# hyone.net
KiCad netlist of a schematic drawn in EAGLE
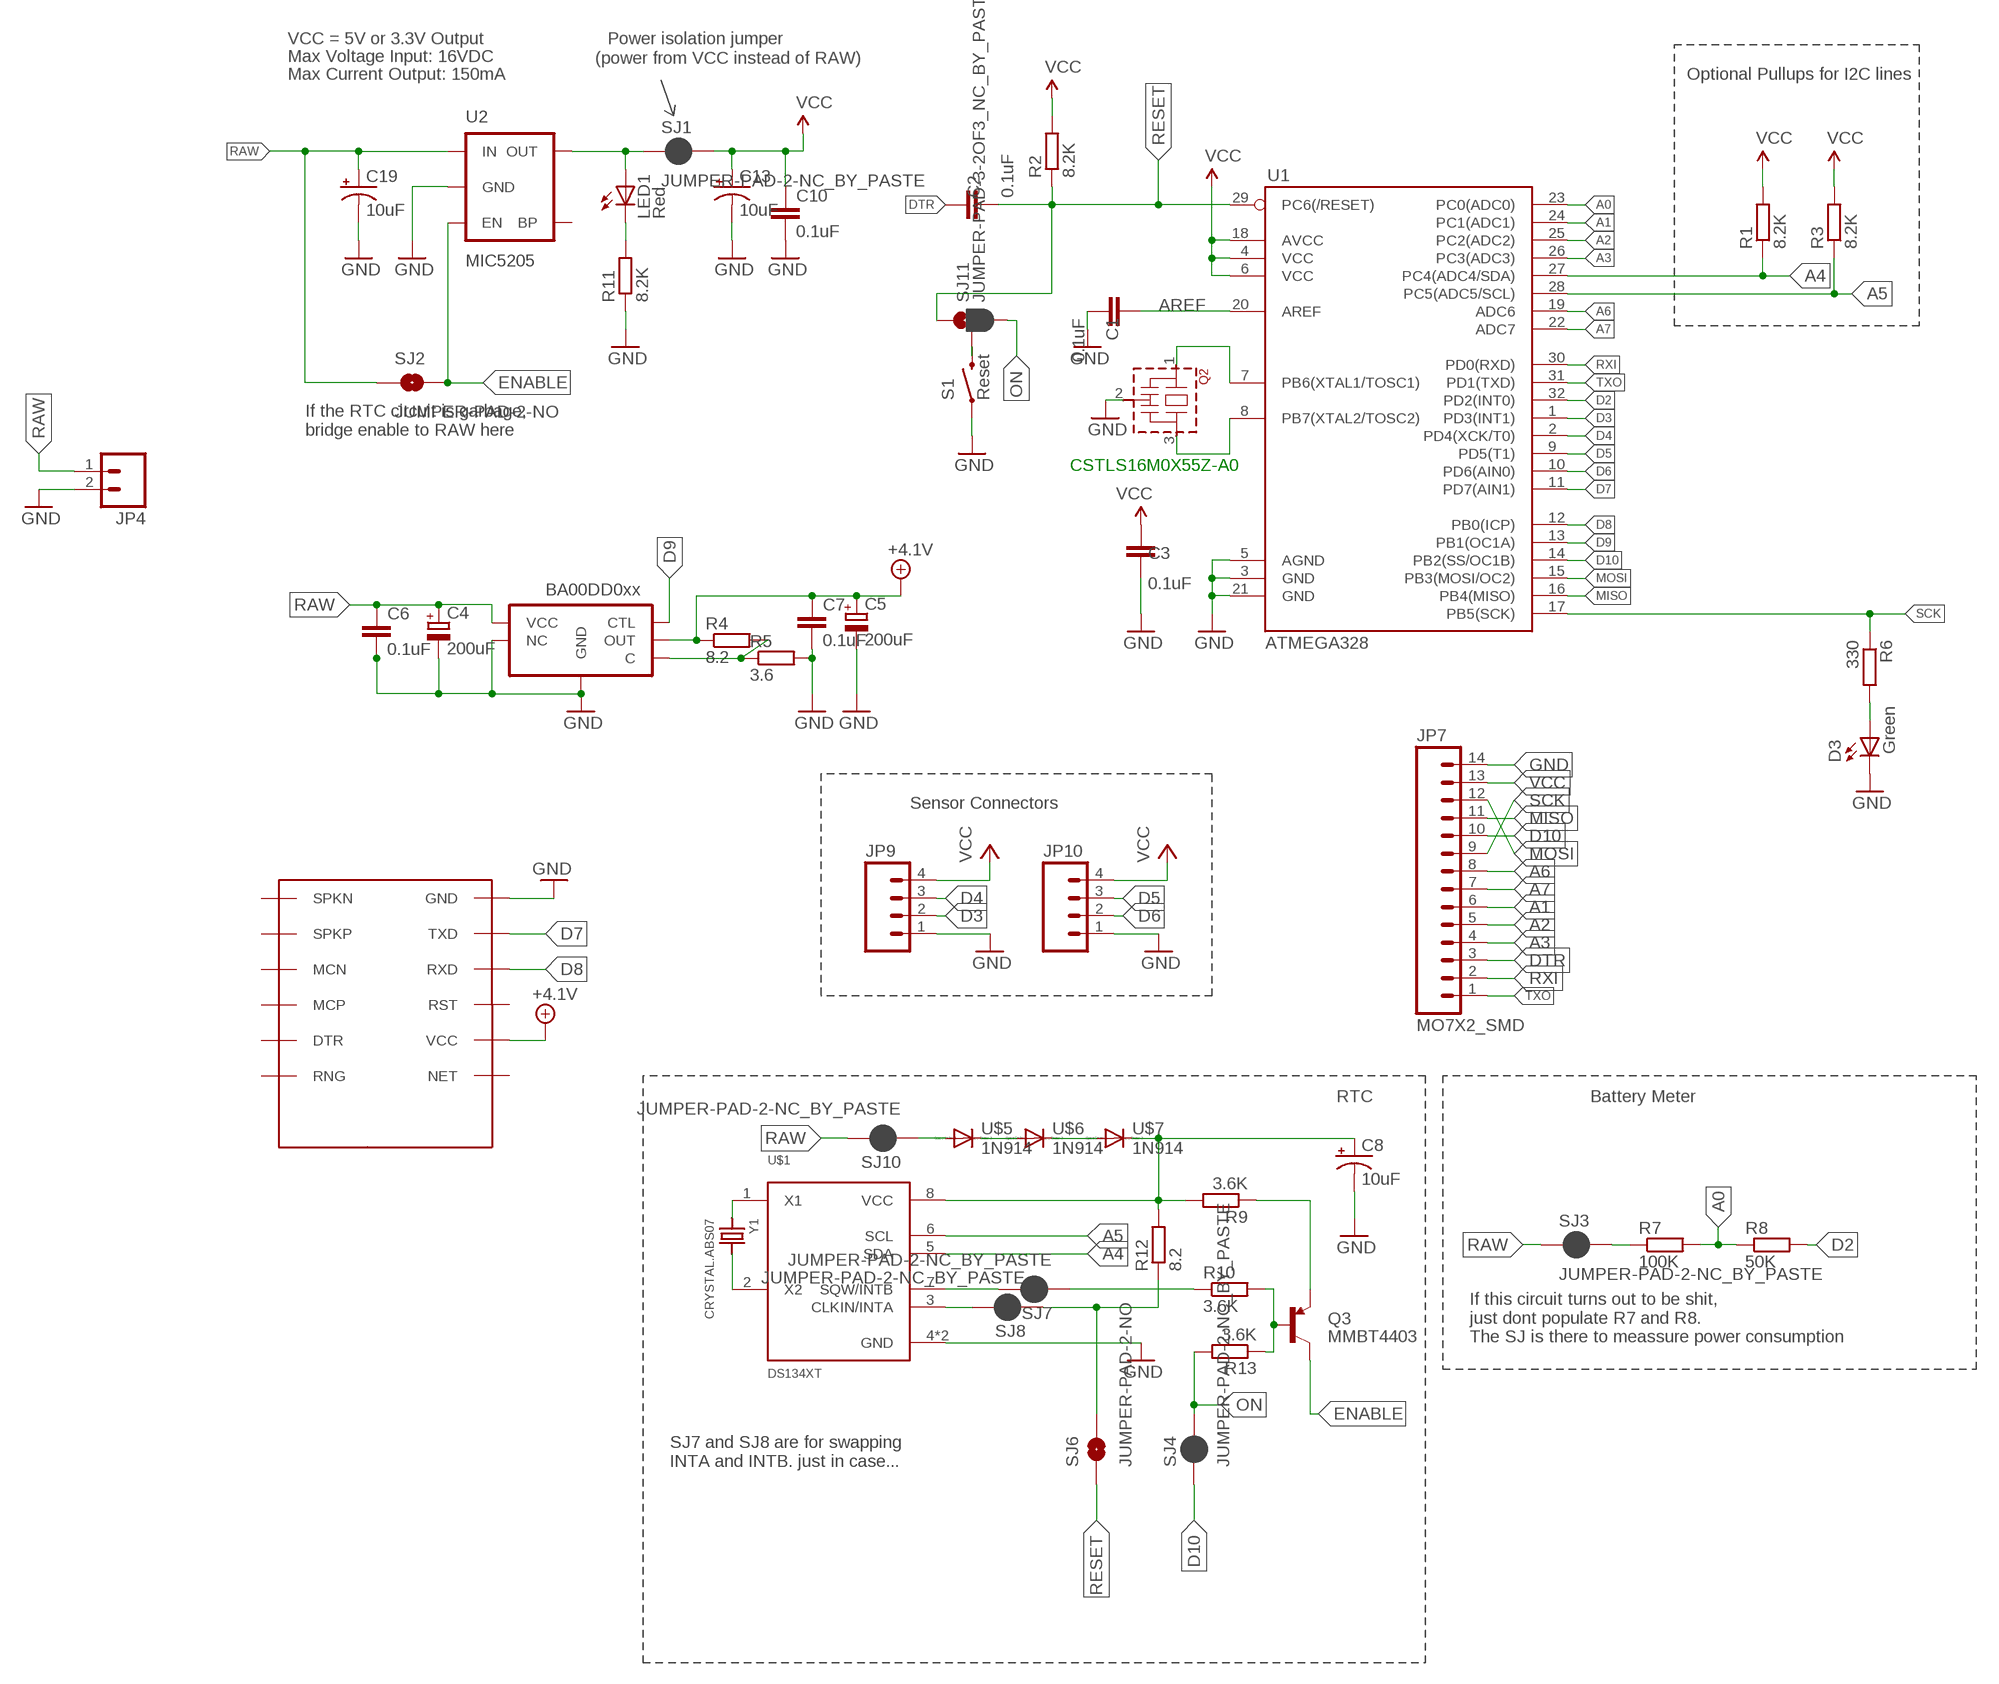
[diagram p0: schematic, sheet 1]

(export (version "E")
  (design (tool "Eeschema 10.0.6"))
  (components
    (comp (ref "C1")
      (value "0.1uF")
      (footprint "eagle-import:C0805")
      (libsource (lib "eagle-import") (part "C-EUC0805"))
    )
    (comp (ref "C2")
      (value "0.1uF")
      (footprint "eagle-import:C0805")
      (libsource (lib "eagle-import") (part "C-EUC0805"))
    )
    (comp (ref "C3")
      (value "0.1uF")
      (footprint "eagle-import:C0805")
      (libsource (lib "eagle-import") (part "C-EUC0805"))
    )
    (comp (ref "C4")
      (value "200uF")
      (footprint "eagle-import:E5-5")
      (libsource (lib "eagle-import") (part "CPOL-EUE5-5"))
    )
    (comp (ref "C5")
      (value "200uF")
      (footprint "eagle-import:E5-5")
      (libsource (lib "eagle-import") (part "CPOL-EUE5-5"))
    )
    (comp (ref "C6")
      (value "0.1uF")
      (footprint "eagle-import:C0805")
      (libsource (lib "eagle-import") (part "C-EUC0805"))
    )
    (comp (ref "C7")
      (value "0.1uF")
      (footprint "eagle-import:C0805")
      (libsource (lib "eagle-import") (part "C-EUC0805"))
    )
    (comp (ref "C8")
      (value "10uF")
      (footprint "eagle-import:EIA3216")
      (libsource (lib "eagle-import") (part "CAP_POL1206"))
    )
    (comp (ref "C10")
      (value "0.1uF")
      (footprint "eagle-import:C0805")
      (libsource (lib "eagle-import") (part "C-EUC0805"))
    )
    (comp (ref "C13")
      (value "10uF")
      (footprint "eagle-import:EIA3216")
      (libsource (lib "eagle-import") (part "CAP_POL1206"))
    )
    (comp (ref "C19")
      (value "10uF")
      (footprint "eagle-import:EIA3216")
      (libsource (lib "eagle-import") (part "CAP_POL1206"))
    )
    (comp (ref "D3")
      (value "Green")
      (footprint "eagle-import:CHIPLED_0805")
      (libsource (lib "eagle-import") (part "LEDCHIPLED_0805"))
    )
    (comp (ref "JP4")
      (value "M02POLAR")
      (footprint "eagle-import:MOLEX-1X2")
      (libsource (lib "eagle-import") (part "M02POLAR"))
    )
    (comp (ref "JP7")
      (value "MO7X2_SMD")
      (footprint "eagle-import:2X7_SMD")
      (libsource (lib "eagle-import") (part "MO7X2_SMD"))
    )
    (comp (ref "JP9")
      (value "M04POLAR")
      (footprint "eagle-import:MOLEX-1X4")
      (libsource (lib "eagle-import") (part "M04POLAR"))
    )
    (comp (ref "JP10")
      (value "M04POLAR")
      (footprint "eagle-import:MOLEX-1X4")
      (libsource (lib "eagle-import") (part "M04POLAR"))
    )
    (comp (ref "LED1")
      (value "Red")
      (footprint "eagle-import:CHIPLED_0805")
      (libsource (lib "eagle-import") (part "LEDCHIPLED_0805"))
    )
    (comp (ref "Q2")
      (value "CSTLS_X")
      (footprint "eagle-import:CSTLS_X")
      (libsource (lib "eagle-import") (part "CSTLS_X"))
    )
    (comp (ref "Q3")
      (value "MMBT4403")
      (footprint "eagle-import:SOT23-3")
      (libsource (lib "eagle-import") (part "TRANSISTOR_PNPMMBT4403"))
    )
    (comp (ref "R1")
      (value "8.2K")
      (footprint "eagle-import:R1206")
      (libsource (lib "eagle-import") (part "R-EU_R1206"))
    )
    (comp (ref "R2")
      (value "8.2K")
      (footprint "eagle-import:R1206")
      (libsource (lib "eagle-import") (part "R-EU_R1206"))
    )
    (comp (ref "R3")
      (value "8.2K")
      (footprint "eagle-import:R1206")
      (libsource (lib "eagle-import") (part "R-EU_R1206"))
    )
    (comp (ref "R4")
      (value "8.2")
      (footprint "eagle-import:R1206")
      (libsource (lib "eagle-import") (part "resistor_R-EU_R1206"))
    )
    (comp (ref "R5")
      (value "3.6")
      (footprint "eagle-import:R1206")
      (libsource (lib "eagle-import") (part "resistor_R-EU_R1206"))
    )
    (comp (ref "R6")
      (value "330")
      (footprint "eagle-import:R1206")
      (libsource (lib "eagle-import") (part "R-EU_R1206"))
    )
    (comp (ref "R7")
      (value "100K")
      (footprint "eagle-import:R1206")
      (libsource (lib "eagle-import") (part "resistor_R-EU_R1206"))
    )
    (comp (ref "R8")
      (value "50K")
      (footprint "eagle-import:R1206")
      (libsource (lib "eagle-import") (part "resistor_R-EU_R1206"))
    )
    (comp (ref "R9")
      (value "3.6K")
      (footprint "eagle-import:R1206")
      (libsource (lib "eagle-import") (part "R-EU_R1206"))
    )
    (comp (ref "R10")
      (value "3.6K")
      (footprint "eagle-import:R1206")
      (libsource (lib "eagle-import") (part "R-EU_R1206"))
    )
    (comp (ref "R11")
      (value "8.2K")
      (footprint "eagle-import:R1206")
      (libsource (lib "eagle-import") (part "R-EU_R1206"))
    )
    (comp (ref "R12")
      (value "8.2")
      (footprint "eagle-import:R1206")
      (libsource (lib "eagle-import") (part "resistor_R-EU_R1206"))
    )
    (comp (ref "R13")
      (value "3.6K")
      (footprint "eagle-import:R1206")
      (libsource (lib "eagle-import") (part "R-EU_R1206"))
    )
    (comp (ref "S1")
      (value "Reset")
      (footprint "eagle-import:TACTILE-SWITCH-SMD-ALT01")
      (libsource (lib "eagle-import") (part "SWITCH-MOMENTARY-2SMD-ALT01"))
    )
    (comp (ref "SJ1")
      (value "JUMPER-PAD-2-NC_BY_PASTE")
      (footprint "eagle-import:PAD-JUMPER-2-NC_BY_PASTE_YES_SILK")
      (libsource (lib "eagle-import") (part "JUMPER-PAD-2-NC_BY_PASTE"))
    )
    (comp (ref "SJ2")
      (value "JUMPER-PAD-2-NO")
      (footprint "eagle-import:PAD-JUMPER-2-NO_NO_SILK")
      (libsource (lib "eagle-import") (part "JUMPER-PAD-2-NO"))
    )
    (comp (ref "SJ3")
      (value "JUMPER-PAD-2-NC_BY_PASTE")
      (footprint "eagle-import:PAD-JUMPER-2-NC_BY_PASTE_YES_SILK")
      (libsource (lib "eagle-import") (part "JUMPER-PAD-2-NC_BY_PASTE"))
    )
    (comp (ref "SJ4")
      (value "JUMPER-PAD-2-NC_BY_PASTE")
      (footprint "eagle-import:PAD-JUMPER-2-NC_BY_PASTE_YES_SILK")
      (libsource (lib "eagle-import") (part "JUMPER-PAD-2-NC_BY_PASTE"))
    )
    (comp (ref "SJ6")
      (value "JUMPER-PAD-2-NO")
      (footprint "eagle-import:PAD-JUMPER-2-NO_NO_SILK")
      (libsource (lib "eagle-import") (part "JUMPER-PAD-2-NO"))
    )
    (comp (ref "SJ7")
      (value "JUMPER-PAD-2-NC_BY_PASTE")
      (footprint "eagle-import:PAD-JUMPER-2-NC_BY_PASTE_YES_SILK")
      (libsource (lib "eagle-import") (part "JUMPER-PAD-2-NC_BY_PASTE"))
    )
    (comp (ref "SJ8")
      (value "JUMPER-PAD-2-NC_BY_PASTE")
      (footprint "eagle-import:PAD-JUMPER-2-NC_BY_PASTE_YES_SILK")
      (libsource (lib "eagle-import") (part "JUMPER-PAD-2-NC_BY_PASTE"))
    )
    (comp (ref "SJ10")
      (value "JUMPER-PAD-2-NC_BY_PASTE")
      (footprint "eagle-import:PAD-JUMPER-2-NC_BY_PASTE_YES_SILK")
      (libsource (lib "eagle-import") (part "JUMPER-PAD-2-NC_BY_PASTE"))
    )
    (comp (ref "SJ11")
      (value "JUMPER-PAD-3-2OF3_NC_BY_PASTE")
      (footprint "eagle-import:PAD-JUMPER-3-2OF3_NC_BY_PASTE_YES_SILK_FULL_BOX")
      (libsource (lib "eagle-import") (part "JUMPER-PAD-3-2OF3_NC_BY_PASTE"))
    )
    (comp (ref "U$1")
      (value "DS134XT")
      (footprint "eagle-import:TDFN-8")
      (libsource (lib "eagle-import") (part "DS134XT"))
    )
    (comp (ref "U$2")
      (value "BA00DD0XX")
      (footprint "eagle-import:HRP5")
      (libsource (lib "eagle-import") (part "BA00DD0XX"))
    )
    (comp (ref "U$4")
      (value "SIM800L")
      (footprint "eagle-import:SIM-CORE")
      (libsource (lib "eagle-import") (part "SIM800L"))
    )
    (comp (ref "U$5")
      (value "1N914")
      (footprint "eagle-import:SOT23")
      (libsource (lib "eagle-import") (part "1N914"))
    )
    (comp (ref "U$6")
      (value "1N914")
      (footprint "eagle-import:SOT23")
      (libsource (lib "eagle-import") (part "1N914"))
    )
    (comp (ref "U$7")
      (value "1N914")
      (footprint "eagle-import:SOT23")
      (libsource (lib "eagle-import") (part "1N914"))
    )
    (comp (ref "U1")
      (value "ATMEGA328")
      (footprint "eagle-import:TQFP32-08")
      (libsource (lib "eagle-import") (part "ATMEGA168"))
    )
    (comp (ref "U2")
      (value "MIC5205")
      (footprint "eagle-import:SOT23-5")
      (libsource (lib "eagle-import") (part "V_REG_LDOSMD"))
    )
    (comp (ref "Y1")
      (value "CRYSTAL.ABS07")
      (footprint "eagle-import:ABS07")
      (libsource (lib "eagle-import") (part "CRYSTAL.ABS07"))
    )
  )
  (nets
    (net (code "1") (name "+4.1V") (class "Default")
      (node (ref "C5") (pin "+") (pinfunction "+_+") (pintype "passive"))
      (node (ref "C7") (pin "1") (pinfunction "1_1") (pintype "passive"))
      (node (ref "R4") (pin "1") (pinfunction "1_1") (pintype "passive"))
      (node (ref "U$2") (pin "4") (pinfunction "OUT_4") (pintype "bidirectional"))
      (node (ref "U$4") (pin "VCC") (pinfunction "VCC_VCC") (pintype "bidirectional"))
    )
    (net (code "2") (name "/AREF") (class "Default")
      (node (ref "C1") (pin "2") (pinfunction "2_2") (pintype "passive"))
      (node (ref "U1") (pin "20") (pinfunction "AREF_20") (pintype "bidirectional"))
    )
    (net (code "3") (name "A0") (class "Default")
      (node (ref "R7") (pin "2") (pinfunction "2_2") (pintype "passive"))
      (node (ref "R8") (pin "1") (pinfunction "1_1") (pintype "passive"))
      (node (ref "U1") (pin "23") (pinfunction "PC0(ADC0)_23") (pintype "bidirectional"))
    )
    (net (code "4") (name "A1") (class "Default")
      (node (ref "JP7") (pin "6") (pinfunction "6_6") (pintype "passive"))
      (node (ref "U1") (pin "24") (pinfunction "PC1(ADC1)_24") (pintype "bidirectional"))
    )
    (net (code "5") (name "A2") (class "Default")
      (node (ref "JP7") (pin "5") (pinfunction "5_5") (pintype "passive"))
      (node (ref "U1") (pin "25") (pinfunction "PC2(ADC2)_25") (pintype "bidirectional"))
    )
    (net (code "6") (name "A3") (class "Default")
      (node (ref "JP7") (pin "4") (pinfunction "4_4") (pintype "passive"))
      (node (ref "U1") (pin "26") (pinfunction "PC3(ADC3)_26") (pintype "bidirectional"))
    )
    (net (code "7") (name "A4") (class "Default")
      (node (ref "R1") (pin "1") (pinfunction "1_1") (pintype "passive"))
      (node (ref "U$1") (pin "5") (pinfunction "SDA_5") (pintype "bidirectional"))
      (node (ref "U1") (pin "27") (pinfunction "PC4(ADC4/SDA)_27") (pintype "bidirectional"))
    )
    (net (code "8") (name "A5") (class "Default")
      (node (ref "R3") (pin "1") (pinfunction "1_1") (pintype "passive"))
      (node (ref "U$1") (pin "6") (pinfunction "SCL_6") (pintype "bidirectional"))
      (node (ref "U1") (pin "28") (pinfunction "PC5(ADC5/SCL)_28") (pintype "bidirectional"))
    )
    (net (code "9") (name "A6") (class "Default")
      (node (ref "JP7") (pin "8") (pinfunction "8_8") (pintype "passive"))
      (node (ref "U1") (pin "19") (pinfunction "ADC6_19") (pintype "bidirectional"))
    )
    (net (code "10") (name "A7") (class "Default")
      (node (ref "JP7") (pin "7") (pinfunction "7_7") (pintype "passive"))
      (node (ref "U1") (pin "22") (pinfunction "ADC7_22") (pintype "bidirectional"))
    )
    (net (code "11") (name "D2") (class "Default")
      (node (ref "R8") (pin "2") (pinfunction "2_2") (pintype "passive"))
      (node (ref "U1") (pin "32") (pinfunction "PD2(INT0)_32") (pintype "bidirectional"))
    )
    (net (code "12") (name "D3") (class "Default")
      (node (ref "JP9") (pin "2") (pinfunction "2_2") (pintype "passive"))
      (node (ref "U1") (pin "1") (pinfunction "PD3(INT1)_1") (pintype "bidirectional"))
    )
    (net (code "13") (name "D4") (class "Default")
      (node (ref "JP9") (pin "3") (pinfunction "3_3") (pintype "passive"))
      (node (ref "U1") (pin "2") (pinfunction "PD4(XCK/T0)_2") (pintype "bidirectional"))
    )
    (net (code "14") (name "D5") (class "Default")
      (node (ref "JP10") (pin "3") (pinfunction "3_3") (pintype "passive"))
      (node (ref "U1") (pin "9") (pinfunction "PD5(T1)_9") (pintype "bidirectional"))
    )
    (net (code "15") (name "D6") (class "Default")
      (node (ref "JP10") (pin "2") (pinfunction "2_2") (pintype "passive"))
      (node (ref "U1") (pin "10") (pinfunction "PD6(AIN0)_10") (pintype "bidirectional"))
    )
    (net (code "16") (name "D7") (class "Default")
      (node (ref "U$4") (pin "TXD") (pinfunction "TXD_TXD") (pintype "bidirectional"))
      (node (ref "U1") (pin "11") (pinfunction "PD7(AIN1)_11") (pintype "bidirectional"))
    )
    (net (code "17") (name "D8") (class "Default")
      (node (ref "U$4") (pin "RXD") (pinfunction "RXD_RXD") (pintype "bidirectional"))
      (node (ref "U1") (pin "12") (pinfunction "PB0(ICP)_12") (pintype "bidirectional"))
    )
    (net (code "18") (name "D9") (class "Default")
      (node (ref "U$2") (pin "1") (pinfunction "CTL_1") (pintype "bidirectional"))
      (node (ref "U1") (pin "13") (pinfunction "PB1(OC1A)_13") (pintype "bidirectional"))
    )
    (net (code "19") (name "D10") (class "Default")
      (node (ref "JP7") (pin "10") (pinfunction "10_10") (pintype "passive"))
      (node (ref "SJ4") (pin "1") (pinfunction "1_1") (pintype "passive"))
      (node (ref "U1") (pin "14") (pinfunction "PB2(SS/OC1B)_14") (pintype "bidirectional"))
    )
    (net (code "20") (name "DTR") (class "Default")
      (node (ref "C2") (pin "2") (pinfunction "2_2") (pintype "passive"))
      (node (ref "JP7") (pin "3") (pinfunction "3_3") (pintype "passive"))
    )
    (net (code "21") (name "ENABLE") (class "Default")
      (node (ref "Q3") (pin "3") (pinfunction "C_3") (pintype "passive"))
      (node (ref "SJ2") (pin "2") (pinfunction "2_2") (pintype "passive"))
      (node (ref "U2") (pin "3") (pinfunction "EN_3") (pintype "input"))
    )
    (net (code "22") (name "GND") (class "Default")
      (node (ref "C1") (pin "1") (pinfunction "1_1") (pintype "passive"))
      (node (ref "C10") (pin "2") (pinfunction "2_2") (pintype "passive"))
      (node (ref "C13") (pin "C") (pinfunction "-_C") (pintype "passive"))
      (node (ref "C19") (pin "C") (pinfunction "-_C") (pintype "passive"))
      (node (ref "C3") (pin "1") (pinfunction "1_1") (pintype "passive"))
      (node (ref "C4") (pin "-") (pinfunction "-_-") (pintype "passive"))
      (node (ref "C5") (pin "-") (pinfunction "-_-") (pintype "passive"))
      (node (ref "C6") (pin "2") (pinfunction "2_2") (pintype "passive"))
      (node (ref "C7") (pin "2") (pinfunction "2_2") (pintype "passive"))
      (node (ref "C8") (pin "C") (pinfunction "-_C") (pintype "passive"))
      (node (ref "D3") (pin "C") (pinfunction "C_C") (pintype "passive"))
      (node (ref "JP10") (pin "1") (pinfunction "1_1") (pintype "passive"))
      (node (ref "JP4") (pin "2") (pinfunction "2_2") (pintype "passive"))
      (node (ref "JP7") (pin "14") (pinfunction "14_14") (pintype "passive"))
      (node (ref "JP9") (pin "1") (pinfunction "1_1") (pintype "passive"))
      (node (ref "Q2") (pin "2") (pinfunction "VSS_2") (pintype "power_in"))
      (node (ref "R11") (pin "1") (pinfunction "1_1") (pintype "passive"))
      (node (ref "R5") (pin "2") (pinfunction "2_2") (pintype "passive"))
      (node (ref "S1") (pin "1") (pinfunction "1_1") (pintype "passive"))
      (node (ref "S1") (pin "2") (pinfunction "1_2") (pintype "passive"))
      (node (ref "U$1") (pin "4") (pinfunction "GND_4") (pintype "bidirectional"))
      (node (ref "U$1") (pin "EP") (pinfunction "GND_EP") (pintype "bidirectional"))
      (node (ref "U$2") (pin "3") (pinfunction "NC_3") (pintype "bidirectional"))
      (node (ref "U$2") (pin "6") (pinfunction "GND_6") (pintype "bidirectional"))
      (node (ref "U$4") (pin "GND") (pinfunction "GND_GND") (pintype "bidirectional"))
      (node (ref "U1") (pin "21") (pinfunction "GND_21") (pintype "bidirectional"))
      (node (ref "U1") (pin "3") (pinfunction "GND_3") (pintype "bidirectional"))
      (node (ref "U1") (pin "5") (pinfunction "AGND_5") (pintype "bidirectional"))
      (node (ref "U2") (pin "2") (pinfunction "GND_2") (pintype "input"))
    )
    (net (code "23") (name "MISO") (class "Default")
      (node (ref "JP7") (pin "11") (pinfunction "11_11") (pintype "passive"))
      (node (ref "U1") (pin "16") (pinfunction "PB4(MISO)_16") (pintype "bidirectional"))
    )
    (net (code "24") (name "MOSI") (class "Default")
      (node (ref "JP7") (pin "12") (pinfunction "12_12") (pintype "passive"))
      (node (ref "U1") (pin "15") (pinfunction "PB3(MOSI/OC2)_15") (pintype "bidirectional"))
    )
    (net (code "25") (name "Net-(C8-+)") (class "Default")
      (node (ref "C8") (pin "A") (pinfunction "+_A") (pintype "passive"))
      (node (ref "R12") (pin "2") (pinfunction "2_2") (pintype "passive"))
      (node (ref "R9") (pin "2") (pinfunction "2_2") (pintype "passive"))
      (node (ref "U$1") (pin "8") (pinfunction "VCC_8") (pintype "bidirectional"))
      (node (ref "U$7") (pin "3") (pinfunction "C_3") (pintype "passive"))
    )
    (net (code "26") (name "Net-(D3-PadA)") (class "Default")
      (node (ref "D3") (pin "A") (pinfunction "A_A") (pintype "passive"))
      (node (ref "R6") (pin "2") (pinfunction "2_2") (pintype "passive"))
    )
    (net (code "27") (name "Net-(LED1-PadC)") (class "Default")
      (node (ref "LED1") (pin "C") (pinfunction "C_C") (pintype "passive"))
      (node (ref "R11") (pin "2") (pinfunction "2_2") (pintype "passive"))
    )
    (net (code "28") (name "Net-(Q3-B)") (class "Default")
      (node (ref "Q3") (pin "1") (pinfunction "B_1") (pintype "passive"))
      (node (ref "R10") (pin "2") (pinfunction "2_2") (pintype "passive"))
      (node (ref "R13") (pin "1") (pinfunction "1_1") (pintype "passive"))
    )
    (net (code "29") (name "Net-(Q3-E)") (class "Default")
      (node (ref "Q3") (pin "2") (pinfunction "E_2") (pintype "passive"))
      (node (ref "R9") (pin "1") (pinfunction "1_1") (pintype "passive"))
    )
    (net (code "30") (name "Net-(R7-Pad1)") (class "Default")
      (node (ref "R7") (pin "1") (pinfunction "1_1") (pintype "passive"))
      (node (ref "SJ3") (pin "2") (pinfunction "2_2") (pintype "passive"))
    )
    (net (code "31") (name "Net-(R10-Pad1)") (class "Default")
      (node (ref "R10") (pin "1") (pinfunction "1_1") (pintype "passive"))
      (node (ref "SJ7") (pin "1") (pinfunction "1_1") (pintype "passive"))
    )
    (net (code "32") (name "Net-(R12-Pad1)") (class "Default")
      (node (ref "R12") (pin "1") (pinfunction "1_1") (pintype "passive"))
      (node (ref "SJ6") (pin "2") (pinfunction "2_2") (pintype "passive"))
      (node (ref "SJ8") (pin "1") (pinfunction "1_1") (pintype "passive"))
    )
    (net (code "33") (name "Net-(S1-2-Pad3)") (class "Default")
      (node (ref "S1") (pin "3") (pinfunction "2_3") (pintype "passive"))
      (node (ref "S1") (pin "4") (pinfunction "2_4") (pintype "passive"))
      (node (ref "SJ11") (pin "2") (pinfunction "2_2") (pintype "passive"))
    )
    (net (code "34") (name "Net-(U$1-CLKIN{slash}INTA)") (class "Default")
      (node (ref "SJ8") (pin "2") (pinfunction "2_2") (pintype "passive"))
      (node (ref "U$1") (pin "3") (pinfunction "CLKIN/INTA_3") (pintype "bidirectional"))
    )
    (net (code "35") (name "Net-(U$1-SQW{slash}INTB)") (class "Default")
      (node (ref "SJ7") (pin "2") (pinfunction "2_2") (pintype "passive"))
      (node (ref "U$1") (pin "7") (pinfunction "SQW/INTB_7") (pintype "bidirectional"))
    )
    (net (code "36") (name "Net-(U$1-X1)") (class "Default")
      (node (ref "U$1") (pin "1") (pinfunction "X1_1") (pintype "bidirectional"))
      (node (ref "Y1") (pin "1") (pinfunction "1_1") (pintype "passive"))
    )
    (net (code "37") (name "Net-(U$1-X2)") (class "Default")
      (node (ref "U$1") (pin "2") (pinfunction "X2_2") (pintype "bidirectional"))
      (node (ref "Y1") (pin "2") (pinfunction "2_2") (pintype "passive"))
    )
    (net (code "38") (name "Net-(U$2-C)") (class "Default")
      (node (ref "R4") (pin "2") (pinfunction "2_2") (pintype "passive"))
      (node (ref "R5") (pin "1") (pinfunction "1_1") (pintype "passive"))
      (node (ref "U$2") (pin "5") (pinfunction "C_5") (pintype "bidirectional"))
    )
    (net (code "39") (name "Net-(U$5-A)") (class "Default")
      (node (ref "SJ10") (pin "1") (pinfunction "1_1") (pintype "passive"))
      (node (ref "U$5") (pin "1") (pinfunction "A_1") (pintype "passive"))
    )
    (net (code "40") (name "Net-(U$5-C)") (class "Default")
      (node (ref "U$5") (pin "3") (pinfunction "C_3") (pintype "passive"))
      (node (ref "U$6") (pin "1") (pinfunction "A_1") (pintype "passive"))
    )
    (net (code "41") (name "Net-(U$6-C)") (class "Default")
      (node (ref "U$6") (pin "3") (pinfunction "C_3") (pintype "passive"))
      (node (ref "U$7") (pin "1") (pinfunction "A_1") (pintype "passive"))
    )
    (net (code "42") (name "Net-(U1-PB6(XTAL1{slash}TOSC1))") (class "Default")
      (node (ref "Q2") (pin "1") (pinfunction "1_1") (pintype "output"))
      (node (ref "U1") (pin "7") (pinfunction "PB6(XTAL1/TOSC1)_7") (pintype "bidirectional"))
    )
    (net (code "43") (name "Net-(U1-PB7(XTAL2{slash}TOSC2))") (class "Default")
      (node (ref "Q2") (pin "3") (pinfunction "3_3") (pintype "input"))
      (node (ref "U1") (pin "8") (pinfunction "PB7(XTAL2/TOSC2)_8") (pintype "bidirectional"))
    )
    (net (code "44") (name "Net-(U2-OUT)") (class "Default")
      (node (ref "LED1") (pin "A") (pinfunction "A_A") (pintype "passive"))
      (node (ref "SJ1") (pin "1") (pinfunction "1_1") (pintype "passive"))
      (node (ref "U2") (pin "5") (pinfunction "OUT_5") (pintype "passive"))
    )
    (net (code "45") (name "ON") (class "Default")
      (node (ref "R13") (pin "2") (pinfunction "2_2") (pintype "passive"))
      (node (ref "SJ11") (pin "3") (pinfunction "3_3") (pintype "passive"))
      (node (ref "SJ4") (pin "2") (pinfunction "2_2") (pintype "passive"))
    )
    (net (code "46") (name "RAW") (class "Default")
      (node (ref "C19") (pin "A") (pinfunction "+_A") (pintype "passive"))
      (node (ref "C4") (pin "+") (pinfunction "+_+") (pintype "passive"))
      (node (ref "C6") (pin "1") (pinfunction "1_1") (pintype "passive"))
      (node (ref "JP4") (pin "1") (pinfunction "1_1") (pintype "passive"))
      (node (ref "SJ10") (pin "2") (pinfunction "2_2") (pintype "passive"))
      (node (ref "SJ2") (pin "1") (pinfunction "1_1") (pintype "passive"))
      (node (ref "SJ3") (pin "1") (pinfunction "1_1") (pintype "passive"))
      (node (ref "U$2") (pin "2") (pinfunction "VCC_2") (pintype "bidirectional"))
      (node (ref "U2") (pin "1") (pinfunction "IN_1") (pintype "input"))
    )
    (net (code "47") (name "RESET") (class "Default")
      (node (ref "C2") (pin "1") (pinfunction "1_1") (pintype "passive"))
      (node (ref "R2") (pin "1") (pinfunction "1_1") (pintype "passive"))
      (node (ref "SJ11") (pin "1") (pinfunction "1_1") (pintype "passive"))
      (node (ref "SJ6") (pin "1") (pinfunction "1_1") (pintype "passive"))
      (node (ref "U1") (pin "29") (pinfunction "PC6(/RESET)_29") (pintype "bidirectional"))
    )
    (net (code "48") (name "RXI") (class "Default")
      (node (ref "JP7") (pin "2") (pinfunction "2_2") (pintype "passive"))
      (node (ref "U1") (pin "30") (pinfunction "PD0(RXD)_30") (pintype "bidirectional"))
    )
    (net (code "49") (name "SCK") (class "Default")
      (node (ref "JP7") (pin "9") (pinfunction "9_9") (pintype "passive"))
      (node (ref "R6") (pin "1") (pinfunction "1_1") (pintype "passive"))
      (node (ref "U1") (pin "17") (pinfunction "PB5(SCK)_17") (pintype "bidirectional"))
    )
    (net (code "50") (name "TXO") (class "Default")
      (node (ref "JP7") (pin "1") (pinfunction "1_1") (pintype "passive"))
      (node (ref "U1") (pin "31") (pinfunction "PD1(TXD)_31") (pintype "bidirectional"))
    )
    (net (code "51") (name "VCC") (class "Default")
      (node (ref "C10") (pin "1") (pinfunction "1_1") (pintype "passive"))
      (node (ref "C13") (pin "A") (pinfunction "+_A") (pintype "passive"))
      (node (ref "C3") (pin "2") (pinfunction "2_2") (pintype "passive"))
      (node (ref "JP10") (pin "4") (pinfunction "4_4") (pintype "passive"))
      (node (ref "JP7") (pin "13") (pinfunction "13_13") (pintype "passive"))
      (node (ref "JP9") (pin "4") (pinfunction "4_4") (pintype "passive"))
      (node (ref "R1") (pin "2") (pinfunction "2_2") (pintype "passive"))
      (node (ref "R2") (pin "2") (pinfunction "2_2") (pintype "passive"))
      (node (ref "R3") (pin "2") (pinfunction "2_2") (pintype "passive"))
      (node (ref "SJ1") (pin "2") (pinfunction "2_2") (pintype "passive"))
      (node (ref "U1") (pin "18") (pinfunction "AVCC_18") (pintype "bidirectional"))
      (node (ref "U1") (pin "4") (pinfunction "VCC_4") (pintype "bidirectional"))
      (node (ref "U1") (pin "6") (pinfunction "VCC_6") (pintype "bidirectional"))
    )
    (net (code "52") (name "unconnected-(U$4-PadDTR)") (class "Default")
      (node (ref "U$4") (pin "DTR") (pinfunction "DTR_DTR") (pintype "bidirectional"))
    )
    (net (code "53") (name "unconnected-(U$4-PadMCN)") (class "Default")
      (node (ref "U$4") (pin "MCN") (pinfunction "MCN_MCN") (pintype "bidirectional"))
    )
    (net (code "54") (name "unconnected-(U$4-PadMCP)") (class "Default")
      (node (ref "U$4") (pin "MCP") (pinfunction "MCP_MCP") (pintype "bidirectional"))
    )
    (net (code "55") (name "unconnected-(U$4-PadNET)") (class "Default")
      (node (ref "U$4") (pin "NET") (pinfunction "NET_NET") (pintype "bidirectional"))
    )
    (net (code "56") (name "unconnected-(U$4-PadRNG)") (class "Default")
      (node (ref "U$4") (pin "RNG") (pinfunction "RNG_RNG") (pintype "bidirectional"))
    )
    (net (code "57") (name "unconnected-(U$4-PadRST)") (class "Default")
      (node (ref "U$4") (pin "RST") (pinfunction "RST_RST") (pintype "bidirectional"))
    )
    (net (code "58") (name "unconnected-(U$4-PadSPKN)") (class "Default")
      (node (ref "U$4") (pin "SPKN") (pinfunction "SPKN_SPKN") (pintype "bidirectional"))
    )
    (net (code "59") (name "unconnected-(U$4-PadSPKP)") (class "Default")
      (node (ref "U$4") (pin "SPKP") (pinfunction "SPKP_SPKP") (pintype "bidirectional"))
    )
    (net (code "60") (name "unconnected-(U2-BP-Pad4)") (class "Default")
      (node (ref "U2") (pin "4") (pinfunction "BP_4") (pintype "input"))
    )
  )
)
